# E-25_Microphone.net
KiCad netlist of a schematic drawn in Altium Designer
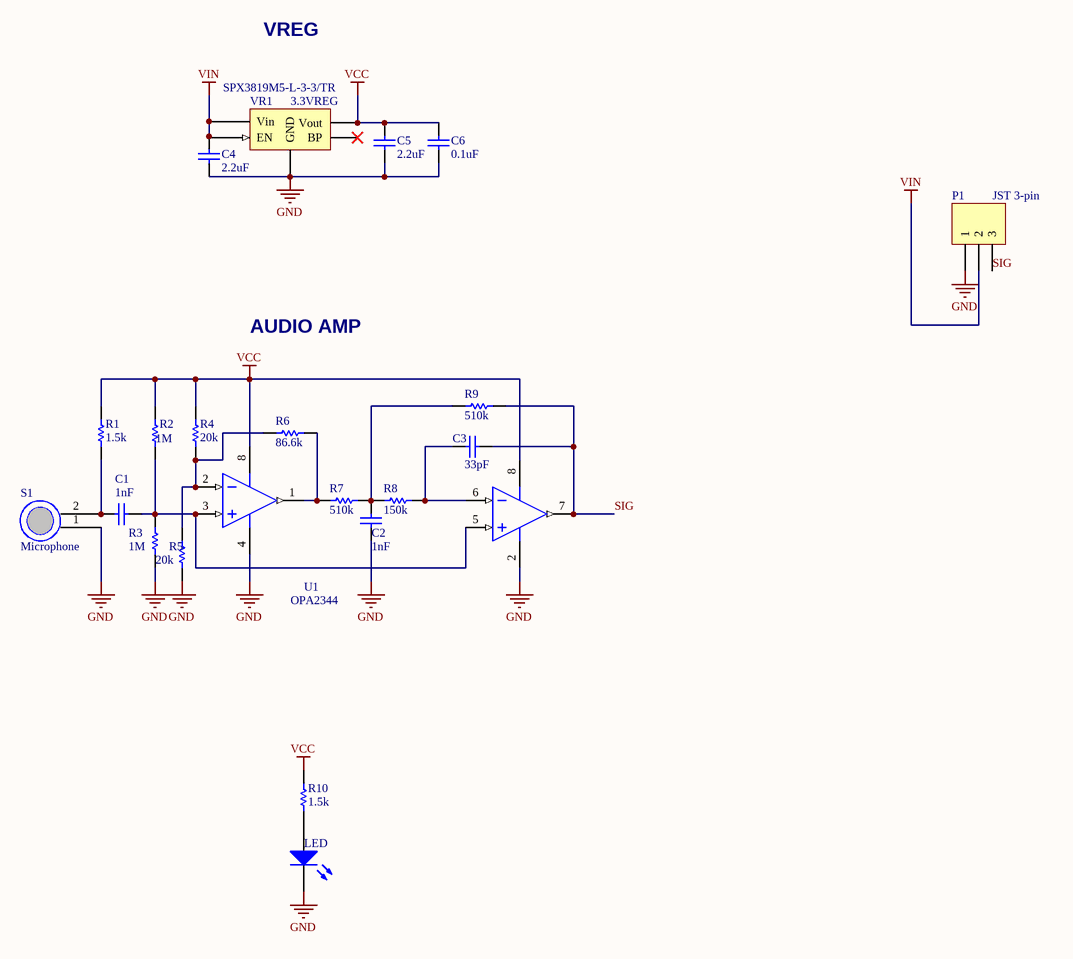
[diagram p0: E-25 Microphone.SchDoc]

(export (version "E")
  (design (tool "Eeschema 10.0.6"))
  (components
    (comp (ref "C1")
      (value "1nF")
      (footprint "0603 TIGHT")
      (description "Capacitor")
      (fields (field (name "Comment") "18pF") (field (name "PUBLISHER") "Altium Limited"))
      (libsource (lib "SB_Discrete") (part "Cap"))
    )
    (comp (ref "C2")
      (value "1nF")
      (footprint "0603 TIGHT")
      (description "Capacitor")
      (fields (field (name "PUBLISHER") "Altium Limited"))
      (libsource (lib "SB_Discrete") (part "Cap"))
    )
    (comp (ref "C3")
      (value "33pF")
      (footprint "0603 TIGHT")
      (description "Capacitor")
      (fields (field (name "Comment") "18pF") (field (name "PUBLISHER") "Altium Limited"))
      (libsource (lib "SB_Discrete") (part "Cap"))
    )
    (comp (ref "C4")
      (value "2.2uF")
      (footprint "0603 TIGHT")
      (description "Capacitor")
      (fields (field (name "PUBLISHER") "Altium Limited"))
      (libsource (lib "SB_Discrete") (part "Cap"))
    )
    (comp (ref "C5")
      (value "2.2uF")
      (footprint "0603 TIGHT")
      (description "Capacitor")
      (fields (field (name "Comment") "100nF") (field (name "PUBLISHER") "Altium Limited"))
      (libsource (lib "SB_Discrete") (part "Cap"))
    )
    (comp (ref "C6")
      (value "0.1uF")
      (footprint "0603 TIGHT")
      (description "Capacitor")
      (fields (field (name "Comment") "100nF") (field (name "PUBLISHER") "Altium Limited"))
      (libsource (lib "SB_Discrete") (part "Cap"))
    )
    (comp (ref "LED")
      (value "LED2")
      (footprint "0805 LED - TIGHT")
      (description "Typical RED GaAs LED")
      (fields (field (name "PUBLISHER") "Altium Limited"))
      (libsource (lib "SB_Discrete") (part "LED1"))
    )
    (comp (ref "P1")
      (value "JST 3-pin")
      (footprint "JST-PH 3-pin SMD")
      (description "Header, 3-Pin")
      (fields (field (name "PUBLISHER") "Altium Limited"))
      (libsource (lib "Miscellaneous Connectors") (part "Header 3"))
    )
    (comp (ref "R1")
      (value "1.5k")
      (footprint "0603 TIGHT")
      (description "Resistor")
      (fields (field (name "Comment") "Res1") (field (name "PUBLISHER") "Altium Limited"))
      (libsource (lib "SB_Discrete") (part "Res1"))
    )
    (comp (ref "R2")
      (value "1M")
      (footprint "0603 TIGHT")
      (description "Resistor")
      (fields (field (name "Comment") "Res1") (field (name "PUBLISHER") "Altium Limited"))
      (libsource (lib "SB_Discrete") (part "Res1"))
    )
    (comp (ref "R3")
      (value "1M")
      (footprint "0603 TIGHT")
      (description "Resistor")
      (fields (field (name "Comment") "Res1") (field (name "PUBLISHER") "Altium Limited"))
      (libsource (lib "SB_Discrete") (part "Res1"))
    )
    (comp (ref "R4")
      (value "20k")
      (footprint "0603 TIGHT")
      (description "Resistor")
      (fields (field (name "Comment") "Res1") (field (name "PUBLISHER") "Altium Limited"))
      (libsource (lib "SB_Discrete") (part "Res1"))
    )
    (comp (ref "R5")
      (value "20k")
      (footprint "0603 TIGHT")
      (description "Resistor")
      (fields (field (name "Comment") "Res1") (field (name "PUBLISHER") "Altium Limited"))
      (libsource (lib "SB_Discrete") (part "Res1"))
    )
    (comp (ref "R6")
      (value "86.6k")
      (footprint "0603 TIGHT")
      (description "Resistor")
      (fields (field (name "Comment") "Res1") (field (name "PUBLISHER") "Altium Limited"))
      (libsource (lib "SB_Discrete") (part "Res1"))
    )
    (comp (ref "R7")
      (value "510k")
      (footprint "0603 TIGHT")
      (description "Resistor")
      (fields (field (name "Comment") "Res1") (field (name "PUBLISHER") "Altium Limited"))
      (libsource (lib "SB_Discrete") (part "Res1"))
    )
    (comp (ref "R8")
      (value "150k")
      (footprint "0603 TIGHT")
      (description "Resistor")
      (fields (field (name "Comment") "Res1") (field (name "PUBLISHER") "Altium Limited"))
      (libsource (lib "SB_Discrete") (part "Res1"))
    )
    (comp (ref "R9")
      (value "510k")
      (footprint "0603 TIGHT")
      (description "Resistor")
      (fields (field (name "Comment") "Res1") (field (name "PUBLISHER") "Altium Limited"))
      (libsource (lib "SB_Discrete") (part "Res1"))
    )
    (comp (ref "R10")
      (value "1.5k")
      (footprint "0603 TIGHT")
      (description "Resistor")
      (fields (field (name "Comment") "Res1") (field (name "PUBLISHER") "Altium Limited"))
      (libsource (lib "SB_Discrete") (part "Res1"))
    )
    (comp (ref "S1")
      (value "Microphone")
      (footprint "MICROPHONE")
      (libsource (lib "SB_Engineered_Components") (part "MIC"))
    )
    (comp (ref "U1")
      (value "OPA2344")
      (footprint "SO-8")
      (libsource (lib "SB_Engineered_Components") (part "OPA2345"))
    )
    (comp (ref "VR1")
      (value "3.3VREG")
      (footprint "SOT-25 New")
      (libsource (lib "SB_Discrete") (part "Vreg SOT25"))
    )
  )
  (nets
    (net (code "1") (name "/SIG") (class "Default")
      (node (ref "C3") (pin "1") (pinfunction "1_1") (pintype "passive"))
      (node (ref "P1") (pin "3") (pinfunction "3_3") (pintype "passive"))
      (node (ref "R9") (pin "1") (pinfunction "1_1") (pintype "passive"))
      (node (ref "U1") (pin "7") (pinfunction "OUTB_7") (pintype "output"))
    )
    (net (code "3") (name "GND") (class "Default")
      (node (ref "C2") (pin "1") (pinfunction "1_1") (pintype "passive"))
      (node (ref "C4") (pin "2") (pinfunction "2_2") (pintype "passive"))
      (node (ref "C5") (pin "2") (pinfunction "2_2") (pintype "passive"))
      (node (ref "C6") (pin "2") (pinfunction "2_2") (pintype "passive"))
      (node (ref "LED") (pin "2") (pinfunction "K_2") (pintype "passive"))
      (node (ref "P1") (pin "1") (pinfunction "1_1") (pintype "passive"))
      (node (ref "R3") (pin "1") (pinfunction "1_1") (pintype "passive"))
      (node (ref "R5") (pin "1") (pinfunction "1_1") (pintype "passive"))
      (node (ref "S1") (pin "1") (pinfunction "1_1") (pintype "passive"))
      (node (ref "U1") (pin "2") (pinfunction "4_2") (pintype "power_in"))
      (node (ref "U1") (pin "4") (pinfunction "V-_4") (pintype "power_in"))
      (node (ref "VR1") (pin "3") (pinfunction "GND_3") (pintype "passive"))
    )
    (net (code "4") (name "Net-(C1-Pad2)") (class "Default")
      (node (ref "C1") (pin "2") (pinfunction "2_2") (pintype "passive"))
      (node (ref "R1") (pin "1") (pinfunction "1_1") (pintype "passive"))
      (node (ref "S1") (pin "2") (pinfunction "2_2") (pintype "passive"))
    )
    (net (code "5") (name "Net-(C2-Pad2)") (class "Default")
      (node (ref "C2") (pin "2") (pinfunction "2_2") (pintype "passive"))
      (node (ref "R7") (pin "1") (pinfunction "1_1") (pintype "passive"))
      (node (ref "R8") (pin "2") (pinfunction "2_2") (pintype "passive"))
      (node (ref "R9") (pin "2") (pinfunction "2_2") (pintype "passive"))
    )
    (net (code "6") (name "Net-(LED-A)") (class "Default")
      (node (ref "LED") (pin "1") (pinfunction "A_1") (pintype "passive"))
      (node (ref "R10") (pin "1") (pinfunction "1_1") (pintype "passive"))
    )
    (net (code "7") (name "Net-(U1-INA+)") (class "Default")
      (node (ref "C1") (pin "1") (pinfunction "1_1") (pintype "passive"))
      (node (ref "R2") (pin "1") (pinfunction "1_1") (pintype "passive"))
      (node (ref "R3") (pin "2") (pinfunction "2_2") (pintype "passive"))
      (node (ref "U1") (pin "3") (pinfunction "INA+_3") (pintype "input"))
      (node (ref "U1") (pin "5") (pinfunction "INB+_5") (pintype "input"))
    )
    (net (code "8") (name "Net-(U1-INA-)") (class "Default")
      (node (ref "R4") (pin "1") (pinfunction "1_1") (pintype "passive"))
      (node (ref "R5") (pin "2") (pinfunction "2_2") (pintype "passive"))
      (node (ref "R6") (pin "2") (pinfunction "2_2") (pintype "passive"))
      (node (ref "U1") (pin "2") (pinfunction "INA-_2") (pintype "input"))
    )
    (net (code "9") (name "Net-(U1-INB-)") (class "Default")
      (node (ref "C3") (pin "2") (pinfunction "2_2") (pintype "passive"))
      (node (ref "R8") (pin "1") (pinfunction "1_1") (pintype "passive"))
      (node (ref "U1") (pin "6") (pinfunction "INB-_6") (pintype "input"))
    )
    (net (code "10") (name "Net-(U1-OUTA)") (class "Default")
      (node (ref "R6") (pin "1") (pinfunction "1_1") (pintype "passive"))
      (node (ref "R7") (pin "2") (pinfunction "2_2") (pintype "passive"))
      (node (ref "U1") (pin "1") (pinfunction "OUTA_1") (pintype "output"))
    )
    (net (code "11") (name "VCC") (class "Default")
      (node (ref "C5") (pin "1") (pinfunction "1_1") (pintype "passive"))
      (node (ref "C6") (pin "1") (pinfunction "1_1") (pintype "passive"))
      (node (ref "R1") (pin "2") (pinfunction "2_2") (pintype "passive"))
      (node (ref "R10") (pin "2") (pinfunction "2_2") (pintype "passive"))
      (node (ref "R2") (pin "2") (pinfunction "2_2") (pintype "passive"))
      (node (ref "R4") (pin "2") (pinfunction "2_2") (pintype "passive"))
      (node (ref "U1") (pin "8") (pinfunction "V+_8") (pintype "power_in"))
      (node (ref "VR1") (pin "2") (pinfunction "Vout_2") (pintype "passive"))
    )
    (net (code "12") (name "VIN") (class "Default")
      (node (ref "C4") (pin "1") (pinfunction "1_1") (pintype "passive"))
      (node (ref "P1") (pin "2") (pinfunction "2_2") (pintype "passive"))
      (node (ref "VR1") (pin "4") (pinfunction "EN_4") (pintype "input"))
      (node (ref "VR1") (pin "5") (pinfunction "Vin_5") (pintype "passive"))
    )
    (net (code "13") (name "unconnected-(VR1-BP-Pad1)") (class "Default")
      (node (ref "VR1") (pin "1") (pinfunction "BP_1") (pintype "passive+no_connect"))
    )
  )
)
